# Snap3.net
KiCad netlist of a schematic drawn in Altium Designer
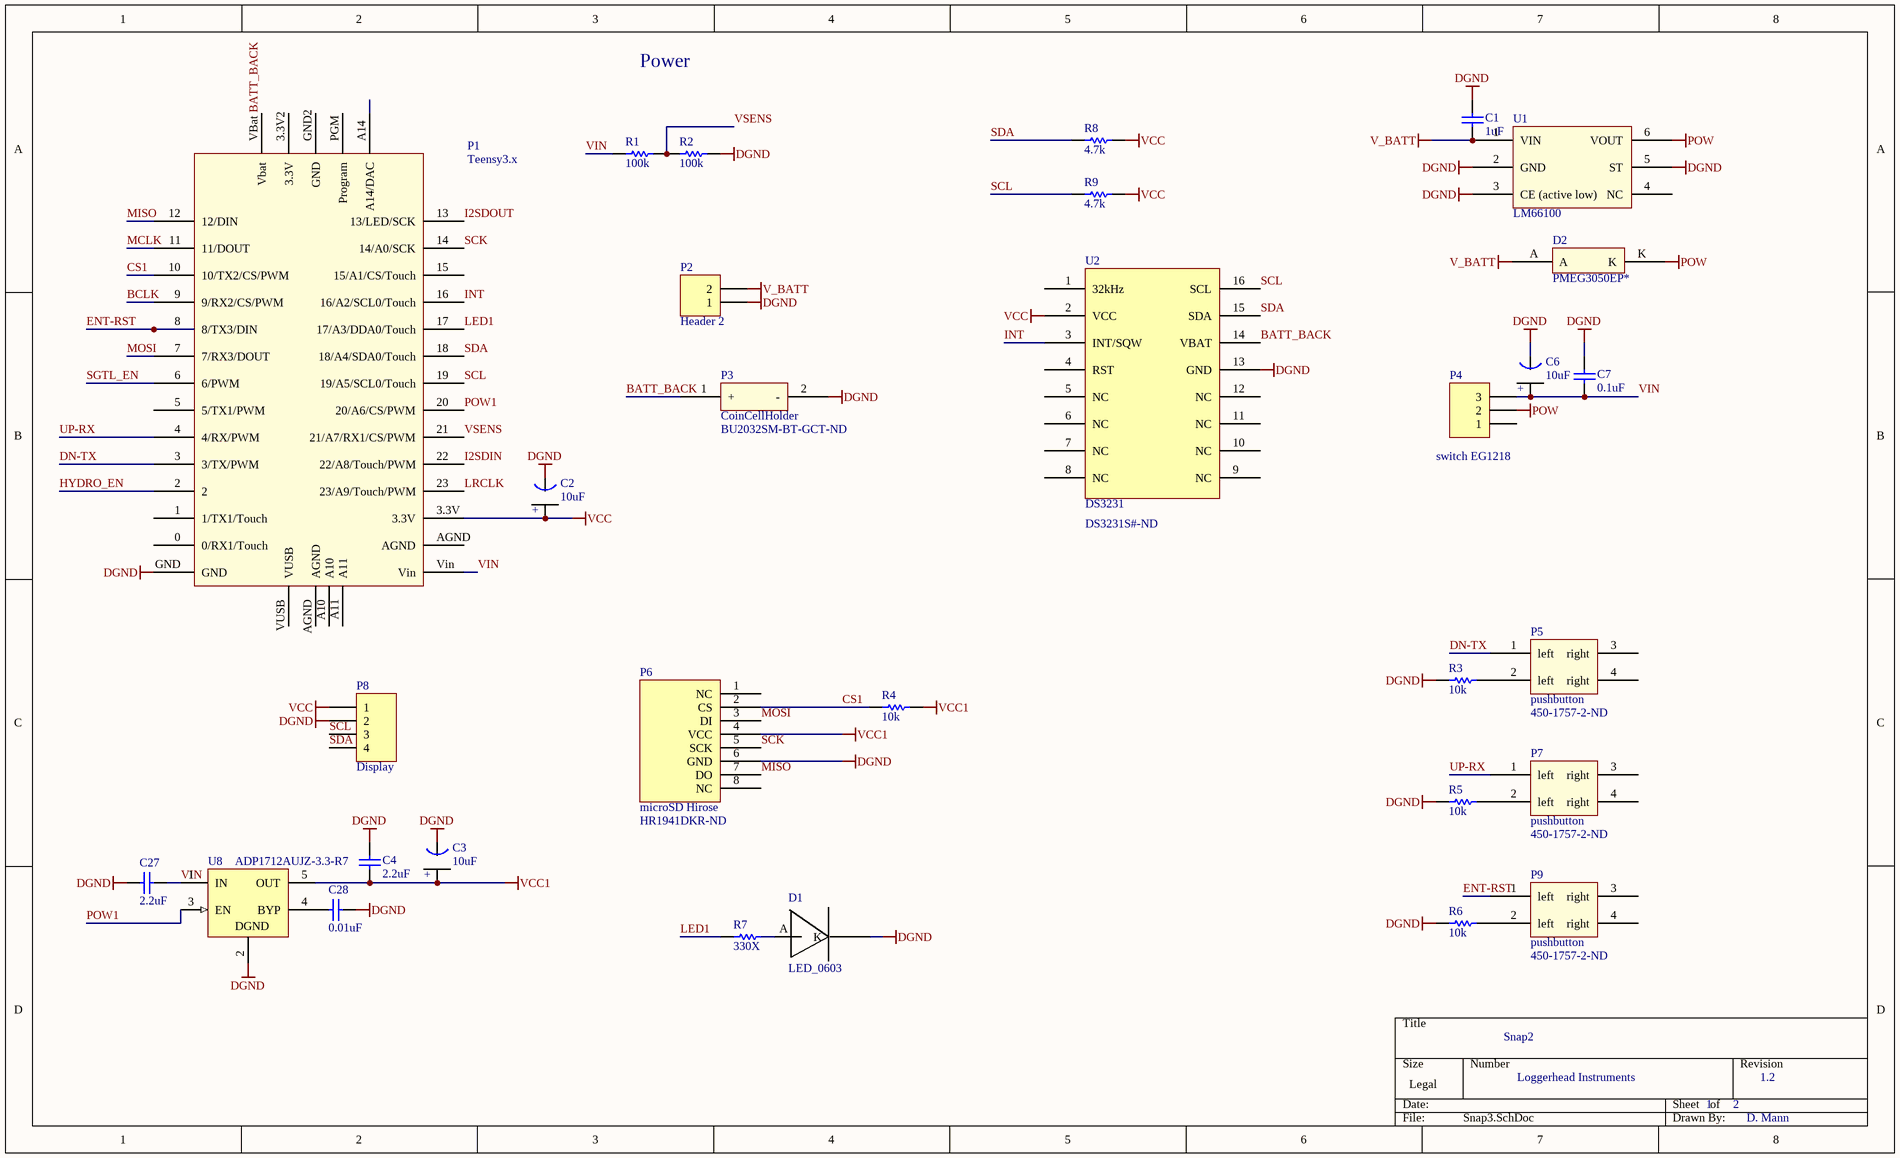
[diagram p0: Snap3.SchDoc]

(export (version "E")
  (design (tool "Eeschema 10.0.6"))
  (components
    (comp (ref "C1")
      (value "1uF")
      (footprint "0402")
      (description "Ceramic Chip Capacitor - Standard")
      (fields (field (name "PUBLISHER") "Altium Limited"))
      (libsource (lib "KEMET Chip Capacitor") (part "C0402"))
    )
    (comp (ref "C2") (value "10uF") (footprint "Tant0805") (libsource (lib "Loggerhead") (part "Tant0805")))
    (comp (ref "C3") (value "10uF") (footprint "Tant0805") (libsource (lib "Loggerhead") (part "Tant0805")))
    (comp (ref "C4")
      (value "2.2uF")
      (footprint "0402")
      (description "Ceramic Chip Capacitor - Standard")
      (fields (field (name "PUBLISHER") "Altium Limited"))
      (libsource (lib "KEMET Chip Capacitor") (part "C0402"))
    )
    (comp (ref "C6") (value "10uF") (footprint "Tant0805") (libsource (lib "Loggerhead") (part "Tant0805")))
    (comp (ref "C7")
      (value "0.1uF")
      (footprint "0402")
      (description "Ceramic Chip Capacitor - Standard")
      (fields (field (name "PUBLISHER") "Altium Limited"))
      (libsource (lib "KEMET Chip Capacitor") (part "C0402"))
    )
    (comp (ref "C27")
      (value "2.2uF")
      (footprint "0402")
      (description "Ceramic Chip Capacitor - Standard")
      (fields (field (name "PUBLISHER") "Altium Limited"))
      (libsource (lib "KEMET Chip Capacitor") (part "C0402"))
    )
    (comp (ref "C28")
      (value "0.01uF")
      (footprint "0402")
      (description "Ceramic Chip Capacitor - Standard")
      (fields (field (name "PUBLISHER") "Altium Limited"))
      (libsource (lib "KEMET Chip Capacitor") (part "C0402"))
    )
    (comp (ref "D1")
      (value "LED_0603")
      (footprint "Diode0603")
      (libsource (lib "Loggerhead") (part "LED_0603"))
    )
    (comp (ref "D2")
      (value "PMEG3050EP*")
      (footprint "Diode_PMEG3050EP")
      (libsource (lib "Loggerhead") (part "Diode_PMEG3050EP"))
    )
    (comp (ref "P1")
      (value "Teensy3.x")
      (footprint "Teensy3.x")
      (libsource (lib "Teensy") (part "Teensy3.x"))
    )
    (comp (ref "P2")
      (value "Header 2")
      (footprint "HDR1X2")
      (description "Header, 2-Pin")
      (fields (field (name "PUBLISHER") "Altium Limited"))
      (libsource (lib "Miscellaneous Connectors") (part "Header 2"))
    )
    (comp (ref "P3")
      (value "CoinCellHolder")
      (footprint "CoinCellHolder")
      (fields (field (name "SUPPLIER PART NUMBER 1") "BU2032SM-BT-GCT-ND"))
      (libsource (lib "Loggerhead") (part "CoinCellHolder"))
    )
    (comp (ref "P4")
      (value "switch EG1218")
      (footprint "HDR1X3")
      (description "Header, 3-Pin")
      (fields (field (name "PUBLISHER") "Altium Limited"))
      (libsource (lib "Miscellaneous Connectors") (part "Header 3"))
    )
    (comp (ref "P5")
      (value "pushbutton")
      (footprint "SOP4")
      (fields (field (name "SUPPLIER PART NUMBER 1") "450-1757-2-ND"))
      (libsource (lib "Loggerhead") (part "pushbutton"))
    )
    (comp (ref "P6")
      (value "microSD Hirose")
      (footprint "DM3D microSD")
      (fields (field (name "SUPPLIER PART NUMBER 1") "HR1941DKR-ND"))
      (libsource (lib "Loggerhead") (part "microSD Hirose"))
    )
    (comp (ref "P7")
      (value "pushbutton")
      (footprint "SOP4")
      (fields (field (name "SUPPLIER PART NUMBER 1") "450-1757-2-ND"))
      (libsource (lib "Loggerhead") (part "pushbutton"))
    )
    (comp (ref "P8")
      (value "Display")
      (footprint "HDR1X4")
      (description "Header, 4-Pin")
      (fields (field (name "PUBLISHER") "Altium Limited"))
      (libsource (lib "Miscellaneous Connectors") (part "Header 4"))
    )
    (comp (ref "P9")
      (value "pushbutton")
      (footprint "SOP4")
      (fields (field (name "SUPPLIER PART NUMBER 1") "450-1757-2-ND"))
      (libsource (lib "Loggerhead") (part "pushbutton"))
    )
    (comp (ref "R1")
      (value "100k")
      (footprint "3-0603")
      (fields (field (name "PUBLISHER") "Altium Limited"))
      (libsource (lib "Panasonic Resistor") (part "ERJ3RK"))
    )
    (comp (ref "R2")
      (value "100k")
      (footprint "3-0603")
      (fields (field (name "PUBLISHER") "Altium Limited"))
      (libsource (lib "Panasonic Resistor") (part "ERJ3RK"))
    )
    (comp (ref "R3")
      (value "10k")
      (footprint "3-0603")
      (fields (field (name "PUBLISHER") "Altium Limited"))
      (libsource (lib "Panasonic Resistor") (part "ERJ3RK"))
    )
    (comp (ref "R4")
      (value "10k")
      (footprint "3-0603")
      (fields (field (name "PUBLISHER") "Altium Limited"))
      (libsource (lib "Panasonic Resistor") (part "ERJ3RK"))
    )
    (comp (ref "R5")
      (value "10k")
      (footprint "3-0603")
      (fields (field (name "PUBLISHER") "Altium Limited"))
      (libsource (lib "Panasonic Resistor") (part "ERJ3RK"))
    )
    (comp (ref "R6")
      (value "10k")
      (footprint "3-0603")
      (fields (field (name "PUBLISHER") "Altium Limited"))
      (libsource (lib "Panasonic Resistor") (part "ERJ3RK"))
    )
    (comp (ref "R7")
      (value "330X")
      (footprint "3-0603")
      (fields (field (name "PUBLISHER") "Altium Limited"))
      (libsource (lib "Panasonic Resistor") (part "ERJ3RK"))
    )
    (comp (ref "R8")
      (value "4.7k")
      (footprint "3-0603")
      (fields (field (name "PUBLISHER") "Altium Limited"))
      (libsource (lib "Panasonic Resistor") (part "ERJ3RK"))
    )
    (comp (ref "R9")
      (value "4.7k")
      (footprint "3-0603")
      (fields (field (name "PUBLISHER") "Altium Limited"))
      (libsource (lib "Panasonic Resistor") (part "ERJ3RK"))
    )
    (comp (ref "U1") (value "LM66100") (footprint "SC-70-6") (libsource (lib "Loggerhead") (part "LM66100")))
    (comp (ref "U2")
      (value "DS3231")
      (footprint "DS3231")
      (fields (field (name "SUPPLIER PART NUMBER 1") "DS3231S#-ND"))
      (libsource (lib "Loggerhead") (part "DS3231"))
    )
    (comp (ref "U8")
      (value "ADP1712AUJZ-3.3-R7")
      (footprint "MF05A_N")
      (description "Micropower, 150mA Low-Noise Ultra Low-Dropout CMOS Voltage Regulator")
      (fields
        (field (name "PARTNUMBER") "LP3985IM5-3.3")
        (field (name "MANUFACTURER") "National Semiconductor")
        (field (name "PUBLISHER") "Altium Limited")
      )
      (libsource (lib "NSC LDO") (part "LP3985IM5-3.3"))
    )
  )
  (nets
    (net (code "1") (name "/BATT_BACK") (class "Default")
      (node (ref "P1") (pin "VBat") (pinfunction "Vbat_VBat") (pintype "passive"))
      (node (ref "P3") (pin "1") (pinfunction "+_1") (pintype "passive"))
      (node (ref "U2") (pin "14") (pinfunction "VBAT_14") (pintype "power_in"))
    )
    (net (code "2") (name "/BCLK") (class "Default")
      (node (ref "P1") (pin "9") (pinfunction "9/RX2/CS/PWM_9") (pintype "passive"))
    )
    (net (code "3") (name "/CS1") (class "Default")
      (node (ref "P1") (pin "10") (pinfunction "10/TX2/CS/PWM_10") (pintype "passive"))
      (node (ref "P6") (pin "2") (pinfunction "CS_2") (pintype "passive"))
      (node (ref "R4") (pin "2") (pinfunction "2_2") (pintype "passive"))
    )
    (net (code "4") (name "/DN-TX") (class "Default")
      (node (ref "P1") (pin "3") (pinfunction "3/TX/PWM_3") (pintype "passive"))
      (node (ref "P5") (pin "1") (pinfunction "left_1") (pintype "passive"))
    )
    (net (code "5") (name "/ENT-RST") (class "Default")
      (node (ref "P1") (pin "8") (pinfunction "8/TX3/DIN_8") (pintype "passive"))
      (node (ref "P9") (pin "1") (pinfunction "left_1") (pintype "passive"))
    )
    (net (code "6") (name "/HYDRO_EN") (class "Default")
      (node (ref "P1") (pin "2") (pinfunction "2_2") (pintype "passive"))
    )
    (net (code "7") (name "/I2SDIN") (class "Default")
      (node (ref "P1") (pin "22") (pinfunction "22/A8/Touch/PWM_22") (pintype "passive"))
    )
    (net (code "8") (name "/I2SDOUT") (class "Default")
      (node (ref "P1") (pin "13") (pinfunction "13/LED/SCK_13") (pintype "passive"))
    )
    (net (code "9") (name "/INT") (class "Default")
      (node (ref "P1") (pin "16") (pinfunction "16/A2/SCL0/Touch_16") (pintype "passive"))
      (node (ref "U2") (pin "3") (pinfunction "INT/SQW_3") (pintype "passive"))
    )
    (net (code "10") (name "/LED1") (class "Default")
      (node (ref "P1") (pin "17") (pinfunction "17/A3/DDA0/Touch_17") (pintype "passive"))
      (node (ref "R7") (pin "1") (pinfunction "1_1") (pintype "passive"))
    )
    (net (code "11") (name "/LRCLK") (class "Default")
      (node (ref "P1") (pin "23") (pinfunction "23/A9/Touch/PWM_23") (pintype "passive"))
    )
    (net (code "12") (name "/MCLK") (class "Default")
      (node (ref "P1") (pin "11") (pinfunction "11/DOUT_11") (pintype "passive"))
    )
    (net (code "13") (name "/MISO") (class "Default")
      (node (ref "P1") (pin "12") (pinfunction "12/DIN_12") (pintype "passive"))
      (node (ref "P6") (pin "7") (pinfunction "DO_7") (pintype "passive"))
    )
    (net (code "14") (name "/MOSI") (class "Default")
      (node (ref "P1") (pin "7") (pinfunction "7/RX3/DOUT_7") (pintype "passive"))
      (node (ref "P6") (pin "3") (pinfunction "DI_3") (pintype "passive"))
    )
    (net (code "15") (name "/POW1") (class "Default")
      (node (ref "P1") (pin "20") (pinfunction "20/A6/CS/PWM_20") (pintype "passive"))
      (node (ref "U8") (pin "3") (pinfunction "EN_3") (pintype "input"))
    )
    (net (code "16") (name "/SCK") (class "Default")
      (node (ref "P1") (pin "14") (pinfunction "14/A0/SCK_14") (pintype "passive"))
      (node (ref "P6") (pin "5") (pinfunction "SCK_5") (pintype "passive"))
    )
    (net (code "17") (name "/SCL") (class "Default")
      (node (ref "P1") (pin "19") (pinfunction "19/A5/SCL0/Touch_19") (pintype "passive"))
      (node (ref "P8") (pin "3") (pinfunction "3_3") (pintype "passive"))
      (node (ref "R9") (pin "1") (pinfunction "1_1") (pintype "passive"))
      (node (ref "U2") (pin "16") (pinfunction "SCL_16") (pintype "passive"))
    )
    (net (code "18") (name "/SDA") (class "Default")
      (node (ref "P1") (pin "18") (pinfunction "18/A4/SDA0/Touch_18") (pintype "passive"))
      (node (ref "P8") (pin "4") (pinfunction "4_4") (pintype "passive"))
      (node (ref "R8") (pin "1") (pinfunction "1_1") (pintype "passive"))
      (node (ref "U2") (pin "15") (pinfunction "SDA_15") (pintype "passive"))
    )
    (net (code "19") (name "/SGTL_EN") (class "Default")
      (node (ref "P1") (pin "6") (pinfunction "6/PWM_6") (pintype "passive"))
    )
    (net (code "20") (name "/UP-RX") (class "Default")
      (node (ref "P1") (pin "4") (pinfunction "4/RX/PWM_4") (pintype "passive"))
      (node (ref "P7") (pin "1") (pinfunction "left_1") (pintype "passive"))
    )
    (net (code "21") (name "/VIN") (class "Default")
      (node (ref "C27") (pin "1") (pinfunction "1_1") (pintype "passive"))
      (node (ref "C6") (pin "2") (pinfunction "+_2") (pintype "passive"))
      (node (ref "C7") (pin "1") (pinfunction "1_1") (pintype "passive"))
      (node (ref "P1") (pin "Vin") (pinfunction "Vin_Vin") (pintype "passive"))
      (node (ref "P4") (pin "3") (pinfunction "3_3") (pintype "passive"))
      (node (ref "R1") (pin "2") (pinfunction "2_2") (pintype "passive"))
      (node (ref "U8") (pin "1") (pinfunction "IN_1") (pintype "power_in"))
    )
    (net (code "22") (name "/VSENS") (class "Default")
      (node (ref "P1") (pin "21") (pinfunction "21/A7/RX1/CS/PWM_21") (pintype "passive"))
      (node (ref "R1") (pin "1") (pinfunction "1_1") (pintype "passive"))
      (node (ref "R2") (pin "2") (pinfunction "2_2") (pintype "passive"))
    )
    (net (code "23") (name "DGND") (class "Default")
      (node (ref "C1") (pin "1") (pinfunction "1_1") (pintype "passive"))
      (node (ref "C2") (pin "1") (pinfunction "GND_1") (pintype "passive"))
      (node (ref "C27") (pin "2") (pinfunction "2_2") (pintype "passive"))
      (node (ref "C28") (pin "2") (pinfunction "2_2") (pintype "passive"))
      (node (ref "C3") (pin "1") (pinfunction "GND_1") (pintype "passive"))
      (node (ref "C4") (pin "2") (pinfunction "2_2") (pintype "passive"))
      (node (ref "C6") (pin "1") (pinfunction "GND_1") (pintype "passive"))
      (node (ref "C7") (pin "2") (pinfunction "2_2") (pintype "passive"))
      (node (ref "D1") (pin "K") (pinfunction "K_K") (pintype "passive"))
      (node (ref "P1") (pin "GND") (pinfunction "GND_GND") (pintype "passive"))
      (node (ref "P2") (pin "1") (pinfunction "1_1") (pintype "passive"))
      (node (ref "P3") (pin "2") (pinfunction "-_2") (pintype "passive"))
      (node (ref "P6") (pin "6") (pinfunction "GND_6") (pintype "passive"))
      (node (ref "P8") (pin "2") (pinfunction "2_2") (pintype "passive"))
      (node (ref "R2") (pin "1") (pinfunction "1_1") (pintype "passive"))
      (node (ref "R3") (pin "2") (pinfunction "2_2") (pintype "passive"))
      (node (ref "R5") (pin "2") (pinfunction "2_2") (pintype "passive"))
      (node (ref "R6") (pin "2") (pinfunction "2_2") (pintype "passive"))
      (node (ref "U1") (pin "2") (pinfunction "GND_2") (pintype "passive"))
      (node (ref "U1") (pin "3") (pinfunction "CE_(active_low)_3") (pintype "passive"))
      (node (ref "U1") (pin "5") (pinfunction "ST_5") (pintype "passive"))
      (node (ref "U2") (pin "13") (pinfunction "GND_13") (pintype "passive"))
      (node (ref "U8") (pin "2") (pinfunction "GND_2") (pintype "power_in"))
    )
    (net (code "24") (name "Net-(D1-PadA)") (class "Default")
      (node (ref "D1") (pin "A") (pinfunction "A_A") (pintype "passive"))
      (node (ref "R7") (pin "2") (pinfunction "2_2") (pintype "passive"))
    )
    (net (code "25") (name "Net-(P5-left-Pad2)") (class "Default")
      (node (ref "P5") (pin "2") (pinfunction "left_2") (pintype "passive"))
      (node (ref "R3") (pin "1") (pinfunction "1_1") (pintype "passive"))
    )
    (net (code "26") (name "Net-(P7-left-Pad2)") (class "Default")
      (node (ref "P7") (pin "2") (pinfunction "left_2") (pintype "passive"))
      (node (ref "R5") (pin "1") (pinfunction "1_1") (pintype "passive"))
    )
    (net (code "27") (name "Net-(P9-left-Pad2)") (class "Default")
      (node (ref "P9") (pin "2") (pinfunction "left_2") (pintype "passive"))
      (node (ref "R6") (pin "1") (pinfunction "1_1") (pintype "passive"))
    )
    (net (code "28") (name "Net-(U8-BYP)") (class "Default")
      (node (ref "C28") (pin "1") (pinfunction "1_1") (pintype "passive"))
      (node (ref "U8") (pin "4") (pinfunction "BYP_4") (pintype "passive"))
    )
    (net (code "29") (name "POW") (class "Default")
      (node (ref "D2") (pin "K") (pinfunction "K_K") (pintype "passive"))
      (node (ref "P4") (pin "2") (pinfunction "2_2") (pintype "passive"))
      (node (ref "U1") (pin "6") (pinfunction "VOUT_6") (pintype "passive"))
    )
    (net (code "30") (name "VCC") (class "Default")
      (node (ref "C2") (pin "2") (pinfunction "+_2") (pintype "passive"))
      (node (ref "P1") (pin "3.3V") (pinfunction "3.3V_3.3V") (pintype "passive"))
      (node (ref "P8") (pin "1") (pinfunction "1_1") (pintype "passive"))
      (node (ref "R8") (pin "2") (pinfunction "2_2") (pintype "passive"))
      (node (ref "R9") (pin "2") (pinfunction "2_2") (pintype "passive"))
      (node (ref "U2") (pin "2") (pinfunction "VCC_2") (pintype "power_in"))
    )
    (net (code "31") (name "VCC1") (class "Default")
      (node (ref "C3") (pin "2") (pinfunction "+_2") (pintype "passive"))
      (node (ref "C4") (pin "1") (pinfunction "1_1") (pintype "passive"))
      (node (ref "P6") (pin "4") (pinfunction "VCC_4") (pintype "passive"))
      (node (ref "R4") (pin "1") (pinfunction "1_1") (pintype "passive"))
      (node (ref "U8") (pin "5") (pinfunction "OUT_5") (pintype "power_in"))
    )
    (net (code "32") (name "V_BATT") (class "Default")
      (node (ref "C1") (pin "2") (pinfunction "2_2") (pintype "passive"))
      (node (ref "D2") (pin "A") (pinfunction "A_A") (pintype "passive"))
      (node (ref "P2") (pin "2") (pinfunction "2_2") (pintype "passive"))
      (node (ref "U1") (pin "1") (pinfunction "VIN_1") (pintype "passive"))
    )
    (net (code "33") (name "unconnected-(P1-0{slash}RX1{slash}Touch-Pad0)") (class "Default")
      (node (ref "P1") (pin "0") (pinfunction "0/RX1/Touch_0") (pintype "passive"))
    )
    (net (code "34") (name "unconnected-(P1-1{slash}TX1{slash}Touch-Pad1)") (class "Default")
      (node (ref "P1") (pin "1") (pinfunction "1/TX1/Touch_1") (pintype "passive"))
    )
    (net (code "35") (name "unconnected-(P1-3.3V-Pad3.3V2)") (class "Default")
      (node (ref "P1") (pin "3.3V2") (pinfunction "3.3V_3.3V2") (pintype "passive"))
    )
    (net (code "36") (name "unconnected-(P1-5{slash}TX1{slash}PWM-Pad5)") (class "Default")
      (node (ref "P1") (pin "5") (pinfunction "5/TX1/PWM_5") (pintype "passive"))
    )
    (net (code "37") (name "unconnected-(P1-15{slash}A1{slash}CS{slash}Touch-Pad15)") (class "Default")
      (node (ref "P1") (pin "15") (pinfunction "15/A1/CS/Touch_15") (pintype "passive"))
    )
    (net (code "38") (name "unconnected-(P1-A14{slash}DAC-PadA14)") (class "Default")
      (node (ref "P1") (pin "A14") (pinfunction "A14/DAC_A14") (pintype "passive"))
    )
    (net (code "39") (name "unconnected-(P1-GND-PadGND2)") (class "Default")
      (node (ref "P1") (pin "GND2") (pinfunction "GND_GND2") (pintype "passive"))
    )
    (net (code "40") (name "unconnected-(P1-PadA10)") (class "Default")
      (node (ref "P1") (pin "A10") (pinfunction "A10_A10") (pintype "passive"))
    )
    (net (code "41") (name "unconnected-(P1-PadA11)") (class "Default")
      (node (ref "P1") (pin "A11") (pinfunction "A11_A11") (pintype "passive"))
    )
    (net (code "42") (name "unconnected-(P1-PadAGND)") (class "Default")
      (node (ref "P1") (pin "AGND") (pinfunction "AGND_AGND") (pintype "passive"))
    )
    (net (code "43") (name "unconnected-(P1-PadAGND)_1") (class "Default")
      (node (ref "P1") (pin "AGND") (pinfunction "AGND_AGND") (pintype "passive"))
    )
    (net (code "44") (name "unconnected-(P1-PadVUSB)") (class "Default")
      (node (ref "P1") (pin "VUSB") (pinfunction "VUSB_VUSB") (pintype "passive"))
    )
    (net (code "45") (name "unconnected-(P1-Program-PadPGM)") (class "Default")
      (node (ref "P1") (pin "PGM") (pinfunction "Program_PGM") (pintype "passive"))
    )
    (net (code "46") (name "unconnected-(P4-Pad1)") (class "Default")
      (node (ref "P4") (pin "1") (pinfunction "1_1") (pintype "passive"))
    )
    (net (code "47") (name "unconnected-(P5-right-Pad3)") (class "Default")
      (node (ref "P5") (pin "3") (pinfunction "right_3") (pintype "passive"))
    )
    (net (code "48") (name "unconnected-(P5-right-Pad4)") (class "Default")
      (node (ref "P5") (pin "4") (pinfunction "right_4") (pintype "passive"))
    )
    (net (code "49") (name "unconnected-(P6-NC-Pad1)") (class "Default")
      (node (ref "P6") (pin "1") (pinfunction "NC_1") (pintype "passive"))
    )
    (net (code "50") (name "unconnected-(P6-NC-Pad8)") (class "Default")
      (node (ref "P6") (pin "8") (pinfunction "NC_8") (pintype "passive"))
    )
    (net (code "51") (name "unconnected-(P7-right-Pad3)") (class "Default")
      (node (ref "P7") (pin "3") (pinfunction "right_3") (pintype "passive"))
    )
    (net (code "52") (name "unconnected-(P7-right-Pad4)") (class "Default")
      (node (ref "P7") (pin "4") (pinfunction "right_4") (pintype "passive"))
    )
    (net (code "53") (name "unconnected-(P9-right-Pad3)") (class "Default")
      (node (ref "P9") (pin "3") (pinfunction "right_3") (pintype "passive"))
    )
    (net (code "54") (name "unconnected-(P9-right-Pad4)") (class "Default")
      (node (ref "P9") (pin "4") (pinfunction "right_4") (pintype "passive"))
    )
    (net (code "55") (name "unconnected-(U1-NC-Pad4)") (class "Default")
      (node (ref "U1") (pin "4") (pinfunction "NC_4") (pintype "passive"))
    )
    (net (code "56") (name "unconnected-(U2-32kHz-Pad1)") (class "Default")
      (node (ref "U2") (pin "1") (pinfunction "32kHz_1") (pintype "passive"))
    )
    (net (code "57") (name "unconnected-(U2-NC-Pad5)") (class "Default")
      (node (ref "U2") (pin "5") (pinfunction "NC_5") (pintype "passive"))
    )
    (net (code "58") (name "unconnected-(U2-NC-Pad6)") (class "Default")
      (node (ref "U2") (pin "6") (pinfunction "NC_6") (pintype "passive"))
    )
    (net (code "59") (name "unconnected-(U2-NC-Pad7)") (class "Default")
      (node (ref "U2") (pin "7") (pinfunction "NC_7") (pintype "passive"))
    )
    (net (code "60") (name "unconnected-(U2-NC-Pad8)") (class "Default")
      (node (ref "U2") (pin "8") (pinfunction "NC_8") (pintype "passive"))
    )
    (net (code "61") (name "unconnected-(U2-NC-Pad9)") (class "Default")
      (node (ref "U2") (pin "9") (pinfunction "NC_9") (pintype "passive"))
    )
    (net (code "62") (name "unconnected-(U2-NC-Pad10)") (class "Default")
      (node (ref "U2") (pin "10") (pinfunction "NC_10") (pintype "passive"))
    )
    (net (code "63") (name "unconnected-(U2-NC-Pad11)") (class "Default")
      (node (ref "U2") (pin "11") (pinfunction "NC_11") (pintype "passive"))
    )
    (net (code "64") (name "unconnected-(U2-NC-Pad12)") (class "Default")
      (node (ref "U2") (pin "12") (pinfunction "NC_12") (pintype "passive"))
    )
    (net (code "65") (name "unconnected-(U2-RST-Pad4)") (class "Default")
      (node (ref "U2") (pin "4") (pinfunction "RST_4") (pintype "passive"))
    )
  )
)
